# untitled1.net
KiCad netlist of a schematic drawn in EAGLE
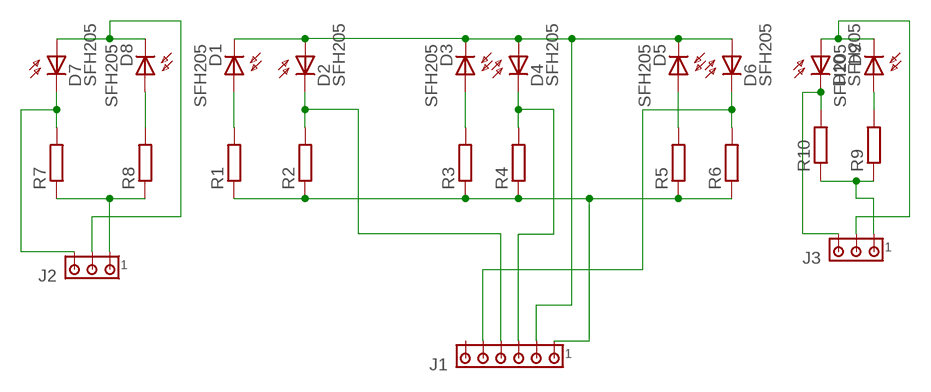
[diagram p0: schematic, sheet 1]

(export (version "E")
  (design (tool "Eeschema 10.0.6"))
  (components
    (comp (ref "D1")
      (value "SFH205")
      (footprint "eagle-import:SFH205")
      (libsource (lib "eagle-import") (part "SFH205"))
    )
    (comp (ref "D2")
      (value "SFH205")
      (footprint "eagle-import:SFH205")
      (libsource (lib "eagle-import") (part "SFH205"))
    )
    (comp (ref "D3")
      (value "SFH205")
      (footprint "eagle-import:SFH205")
      (libsource (lib "eagle-import") (part "SFH205"))
    )
    (comp (ref "D4")
      (value "SFH205")
      (footprint "eagle-import:SFH205")
      (libsource (lib "eagle-import") (part "SFH205"))
    )
    (comp (ref "D5")
      (value "SFH205")
      (footprint "eagle-import:SFH205")
      (libsource (lib "eagle-import") (part "SFH205"))
    )
    (comp (ref "D6")
      (value "SFH205")
      (footprint "eagle-import:SFH205")
      (libsource (lib "eagle-import") (part "SFH205"))
    )
    (comp (ref "D7")
      (value "SFH205")
      (footprint "eagle-import:SFH205")
      (libsource (lib "eagle-import") (part "SFH205"))
    )
    (comp (ref "D8")
      (value "SFH205")
      (footprint "eagle-import:SFH205")
      (libsource (lib "eagle-import") (part "SFH205"))
    )
    (comp (ref "D9")
      (value "SFH205")
      (footprint "eagle-import:SFH205")
      (libsource (lib "eagle-import") (part "SFH205"))
    )
    (comp (ref "D10")
      (value "SFH205")
      (footprint "eagle-import:SFH205")
      (libsource (lib "eagle-import") (part "SFH205"))
    )
    (comp (ref "J1")
      (value "MTA06-100")
      (footprint "eagle-import:10X06MTA")
      (libsource (lib "eagle-import") (part "MTA06-100"))
    )
    (comp (ref "J2")
      (value "MTA03-100")
      (footprint "eagle-import:10X03MTA")
      (libsource (lib "eagle-import") (part "MTA03-100"))
    )
    (comp (ref "J3")
      (value "MTA03-100")
      (footprint "eagle-import:10X03MTA")
      (libsource (lib "eagle-import") (part "MTA03-100"))
    )
    (comp (ref "R1")
      (value "R-EU_0207/10")
      (footprint "eagle-import:0207_10")
      (libsource (lib "eagle-import") (part "R-EU_0207/10"))
    )
    (comp (ref "R2")
      (value "R-EU_0207/10")
      (footprint "eagle-import:0207_10")
      (libsource (lib "eagle-import") (part "R-EU_0207/10"))
    )
    (comp (ref "R3")
      (value "R-EU_0207/10")
      (footprint "eagle-import:0207_10")
      (libsource (lib "eagle-import") (part "R-EU_0207/10"))
    )
    (comp (ref "R4")
      (value "R-EU_0207/10")
      (footprint "eagle-import:0207_10")
      (libsource (lib "eagle-import") (part "R-EU_0207/10"))
    )
    (comp (ref "R5")
      (value "R-EU_0207/10")
      (footprint "eagle-import:0207_10")
      (libsource (lib "eagle-import") (part "R-EU_0207/10"))
    )
    (comp (ref "R6")
      (value "R-EU_0207/10")
      (footprint "eagle-import:0207_10")
      (libsource (lib "eagle-import") (part "R-EU_0207/10"))
    )
    (comp (ref "R7")
      (value "R-EU_0207/10")
      (footprint "eagle-import:0207_10")
      (libsource (lib "eagle-import") (part "R-EU_0207/10"))
    )
    (comp (ref "R8")
      (value "R-EU_0207/10")
      (footprint "eagle-import:0207_10")
      (libsource (lib "eagle-import") (part "R-EU_0207/10"))
    )
    (comp (ref "R9")
      (value "R-EU_0207/10")
      (footprint "eagle-import:0207_10")
      (libsource (lib "eagle-import") (part "R-EU_0207/10"))
    )
    (comp (ref "R10")
      (value "R-EU_0207/10")
      (footprint "eagle-import:0207_10")
      (libsource (lib "eagle-import") (part "R-EU_0207/10"))
    )
  )
  (nets
    (net (code "1") (name "Net-(D1-C)") (class "Default")
      (node (ref "D1") (pin "K") (pinfunction "C_K") (pintype "passive"))
      (node (ref "D2") (pin "A") (pinfunction "A_A") (pintype "passive"))
      (node (ref "D3") (pin "K") (pinfunction "C_K") (pintype "passive"))
      (node (ref "D4") (pin "A") (pinfunction "A_A") (pintype "passive"))
      (node (ref "D5") (pin "K") (pinfunction "C_K") (pintype "passive"))
      (node (ref "D6") (pin "A") (pinfunction "A_A") (pintype "passive"))
      (node (ref "J1") (pin "5") (pinfunction "2_5") (pintype "passive"))
    )
    (net (code "2") (name "Net-(D1-PadA)") (class "Default")
      (node (ref "D1") (pin "A") (pinfunction "A_A") (pintype "passive"))
      (node (ref "R1") (pin "2") (pinfunction "2_2") (pintype "passive"))
    )
    (net (code "3") (name "Net-(D2-C)") (class "Default")
      (node (ref "D2") (pin "K") (pinfunction "C_K") (pintype "passive"))
      (node (ref "J1") (pin "3") (pinfunction "4_3") (pintype "passive"))
      (node (ref "R2") (pin "2") (pinfunction "2_2") (pintype "passive"))
    )
    (net (code "4") (name "Net-(D3-PadA)") (class "Default")
      (node (ref "D3") (pin "A") (pinfunction "A_A") (pintype "passive"))
      (node (ref "R3") (pin "2") (pinfunction "2_2") (pintype "passive"))
    )
    (net (code "5") (name "Net-(D4-C)") (class "Default")
      (node (ref "D4") (pin "K") (pinfunction "C_K") (pintype "passive"))
      (node (ref "J1") (pin "4") (pinfunction "3_4") (pintype "passive"))
      (node (ref "R4") (pin "2") (pinfunction "2_2") (pintype "passive"))
    )
    (net (code "6") (name "Net-(D5-PadA)") (class "Default")
      (node (ref "D5") (pin "A") (pinfunction "A_A") (pintype "passive"))
      (node (ref "R5") (pin "2") (pinfunction "2_2") (pintype "passive"))
    )
    (net (code "7") (name "Net-(D6-C)") (class "Default")
      (node (ref "D6") (pin "K") (pinfunction "C_K") (pintype "passive"))
      (node (ref "J1") (pin "2") (pinfunction "5_2") (pintype "passive"))
      (node (ref "R6") (pin "2") (pinfunction "2_2") (pintype "passive"))
    )
    (net (code "8") (name "Net-(D7-C)") (class "Default")
      (node (ref "D7") (pin "K") (pinfunction "C_K") (pintype "passive"))
      (node (ref "J2") (pin "3") (pinfunction "3_3") (pintype "passive"))
      (node (ref "R7") (pin "2") (pinfunction "2_2") (pintype "passive"))
    )
    (net (code "9") (name "Net-(D8-C)") (class "Default")
      (node (ref "D7") (pin "A") (pinfunction "A_A") (pintype "passive"))
      (node (ref "D8") (pin "K") (pinfunction "C_K") (pintype "passive"))
      (node (ref "J2") (pin "2") (pinfunction "2_2") (pintype "passive"))
    )
    (net (code "10") (name "Net-(D8-PadA)") (class "Default")
      (node (ref "D8") (pin "A") (pinfunction "A_A") (pintype "passive"))
      (node (ref "R8") (pin "2") (pinfunction "2_2") (pintype "passive"))
    )
    (net (code "11") (name "Net-(D9-C)") (class "Default")
      (node (ref "D10") (pin "A") (pinfunction "A_A") (pintype "passive"))
      (node (ref "D9") (pin "K") (pinfunction "C_K") (pintype "passive"))
      (node (ref "J3") (pin "2") (pinfunction "2_2") (pintype "passive"))
    )
    (net (code "12") (name "Net-(D9-PadA)") (class "Default")
      (node (ref "D9") (pin "A") (pinfunction "A_A") (pintype "passive"))
      (node (ref "R9") (pin "2") (pinfunction "2_2") (pintype "passive"))
    )
    (net (code "13") (name "Net-(D10-C)") (class "Default")
      (node (ref "D10") (pin "K") (pinfunction "C_K") (pintype "passive"))
      (node (ref "J3") (pin "3") (pinfunction "3_3") (pintype "passive"))
      (node (ref "R10") (pin "2") (pinfunction "2_2") (pintype "passive"))
    )
    (net (code "14") (name "Net-(J1-1)") (class "Default")
      (node (ref "J1") (pin "6") (pinfunction "1_6") (pintype "passive"))
      (node (ref "R1") (pin "1") (pinfunction "1_1") (pintype "passive"))
      (node (ref "R2") (pin "1") (pinfunction "1_1") (pintype "passive"))
      (node (ref "R3") (pin "1") (pinfunction "1_1") (pintype "passive"))
      (node (ref "R4") (pin "1") (pinfunction "1_1") (pintype "passive"))
      (node (ref "R5") (pin "1") (pinfunction "1_1") (pintype "passive"))
      (node (ref "R6") (pin "1") (pinfunction "1_1") (pintype "passive"))
    )
    (net (code "15") (name "Net-(J2-Pad1)") (class "Default")
      (node (ref "J2") (pin "1") (pinfunction "1_1") (pintype "passive"))
      (node (ref "R7") (pin "1") (pinfunction "1_1") (pintype "passive"))
      (node (ref "R8") (pin "1") (pinfunction "1_1") (pintype "passive"))
    )
    (net (code "16") (name "Net-(J3-Pad1)") (class "Default")
      (node (ref "J3") (pin "1") (pinfunction "1_1") (pintype "passive"))
      (node (ref "R10") (pin "1") (pinfunction "1_1") (pintype "passive"))
      (node (ref "R9") (pin "1") (pinfunction "1_1") (pintype "passive"))
    )
    (net (code "17") (name "unconnected-(J1-6-Pad1)") (class "Default")
      (node (ref "J1") (pin "1") (pinfunction "6_1") (pintype "passive"))
    )
  )
)
